# Zio_Qwiic_LoRa_Module.net
KiCad netlist of a schematic drawn in EAGLE
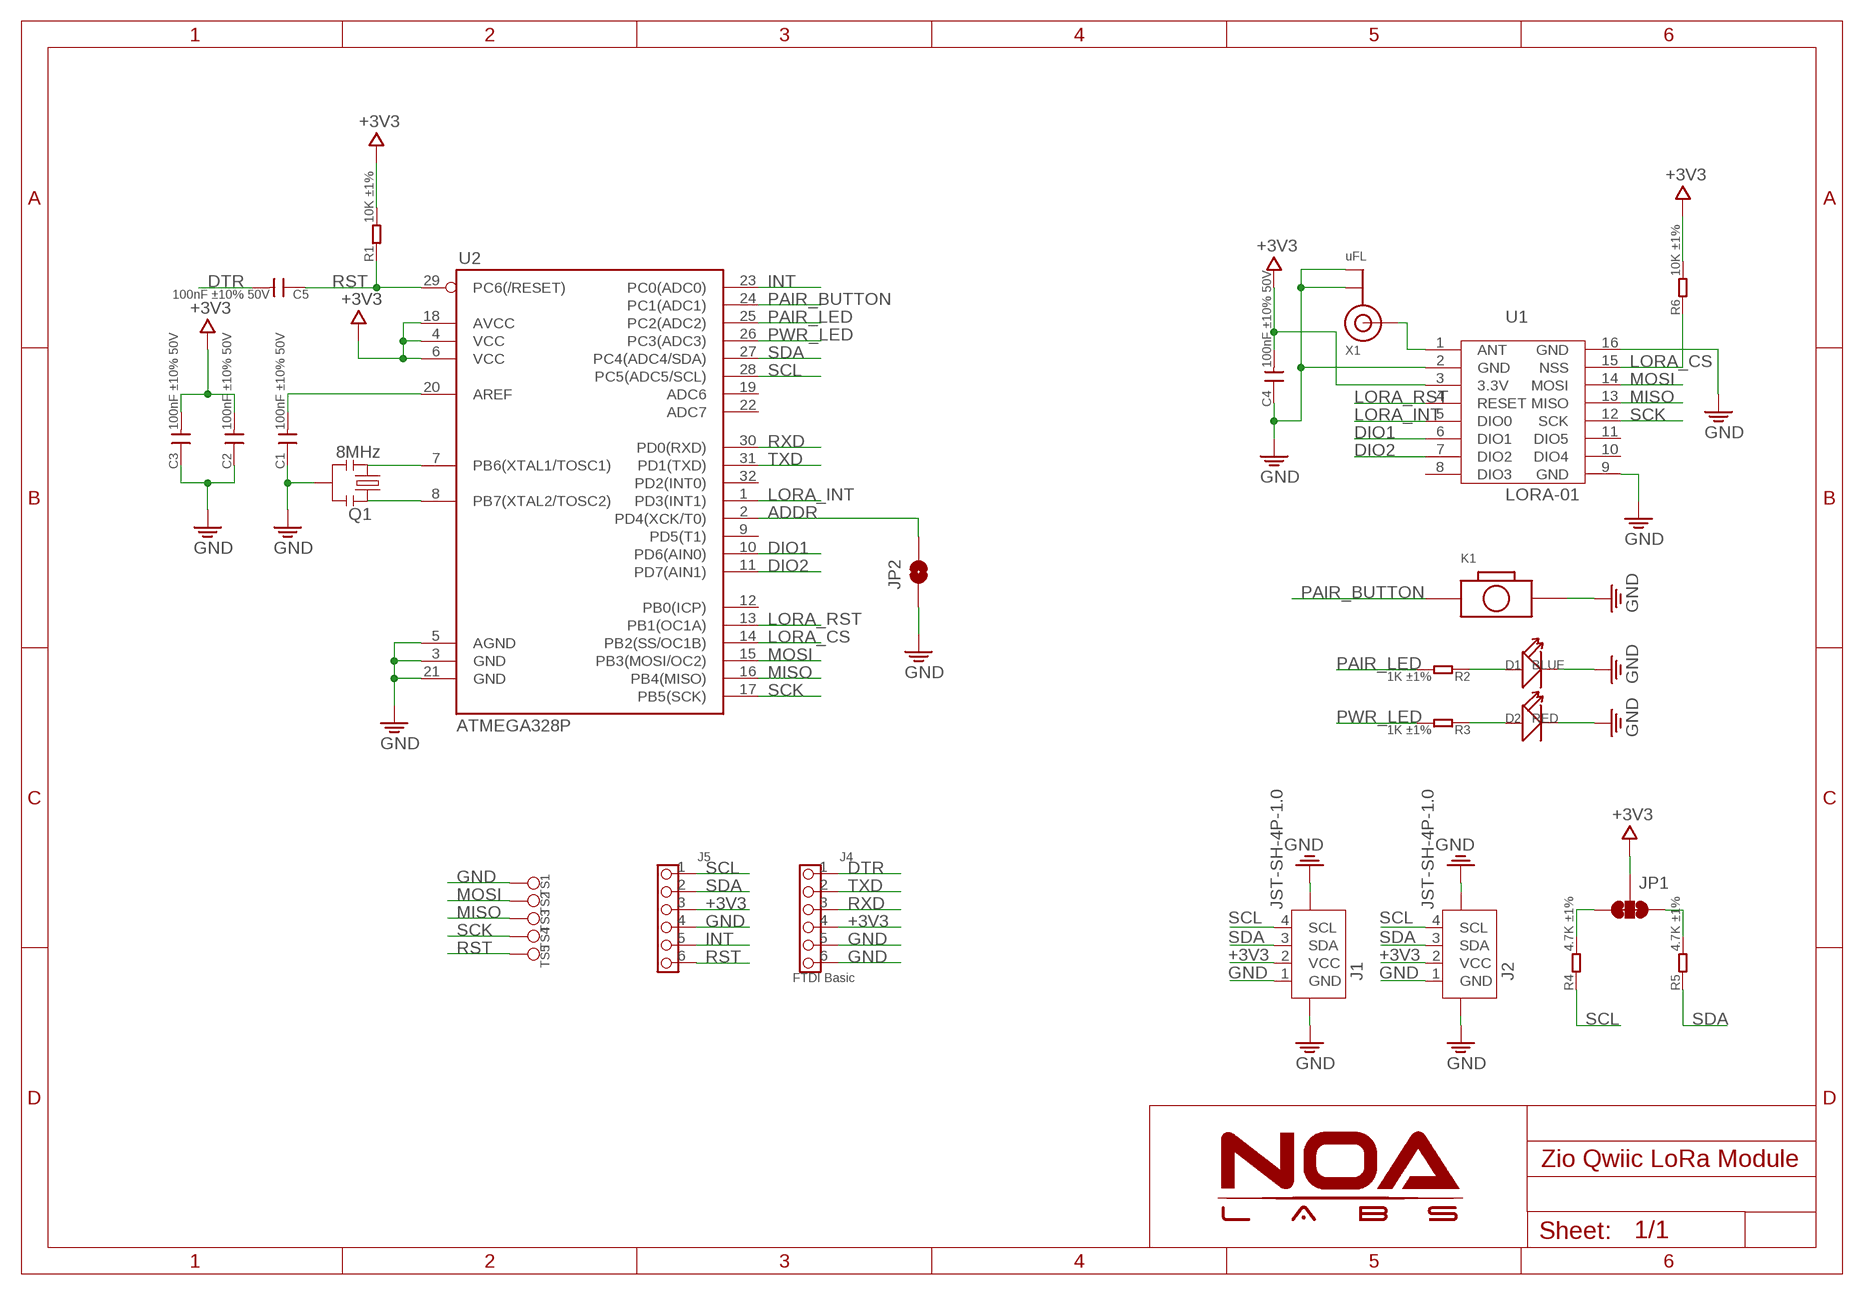
[diagram p0: schematic, sheet 1]

(export (version "E")
  (design (tool "Eeschema 10.0.6"))
  (components
    (comp (ref "C1")
      (value "100nF ±10% 50V")
      (footprint "eagle-import:C0603")
      (libsource (lib "eagle-import") (part "C-0603"))
    )
    (comp (ref "C2")
      (value "100nF ±10% 50V")
      (footprint "eagle-import:C0603")
      (libsource (lib "eagle-import") (part "C-0603"))
    )
    (comp (ref "C3")
      (value "100nF ±10% 50V")
      (footprint "eagle-import:C0603")
      (libsource (lib "eagle-import") (part "C-0603"))
    )
    (comp (ref "C4")
      (value "100nF ±10% 50V")
      (footprint "eagle-import:C0603")
      (libsource (lib "eagle-import") (part "C-0603"))
    )
    (comp (ref "C5")
      (value "100nF ±10% 50V")
      (footprint "eagle-import:C0603")
      (libsource (lib "eagle-import") (part "C-0603"))
    )
    (comp (ref "D1")
      (value "BLUE")
      (footprint "eagle-import:LED-0603")
      (libsource (lib "eagle-import") (part "LED'0603'"))
    )
    (comp (ref "D2")
      (value "RED")
      (footprint "eagle-import:LED-0603")
      (libsource (lib "eagle-import") (part "LED'0603'"))
    )
    (comp (ref "J1")
      (value "JST-SH-4P-1.0")
      (footprint "eagle-import:JST-SH-4P")
      (libsource (lib "eagle-import") (part "JST-SH-4P-1.0"))
    )
    (comp (ref "J2")
      (value "JST-SH-4P-1.0")
      (footprint "eagle-import:JST-SH-4P")
      (libsource (lib "eagle-import") (part "JST-SH-4P-1.0"))
    )
    (comp (ref "J4")
      (value "FTDI Basic")
      (footprint "eagle-import:6P-2.54-60_35MIL")
      (libsource (lib "eagle-import") (part "HEADER-6P-60/35MIL"))
    )
    (comp (ref "J5")
      (value "HEADER-6P-60/35MIL")
      (footprint "eagle-import:6P-2.54-60_35MIL")
      (libsource (lib "eagle-import") (part "HEADER-6P-60/35MIL"))
    )
    (comp (ref "JP1")
      (value "SMT-JUMPER_3_2-NC_TRACE")
      (footprint "eagle-import:SMT-JUMPER_3_2-NC_TRACE")
      (libsource (lib "eagle-import") (part "SMT-JUMPER_3_2-NC_TRACE"))
    )
    (comp (ref "JP2")
      (value "JUMPER-SMT_2_NC_PASTE_NOCREM")
      (footprint "eagle-import:SMT-JUMPER_2_NC_PASTE_SILK_NOCREM")
      (libsource (lib "eagle-import") (part "JUMPER-SMT_2_NC_PASTE_NOCREM"))
    )
    (comp (ref "K1")
      (value "BOTTON-2PSKRKAEE020")
      (footprint "eagle-import:SKRKAEE020")
      (libsource (lib "eagle-import") (part "BOTTON-2PSKRKAEE020"))
    )
    (comp (ref "Q1")
      (value "8MHz")
      (footprint "eagle-import:RESONATOR-SMD")
      (libsource (lib "eagle-import") (part "RESONATORSMD"))
    )
    (comp (ref "R1")
      (value "10K ±1%")
      (footprint "eagle-import:R0603")
      (libsource (lib "eagle-import") (part "R-0603"))
    )
    (comp (ref "R2")
      (value "1K ±1%")
      (footprint "eagle-import:R0603")
      (libsource (lib "eagle-import") (part "R-0603"))
    )
    (comp (ref "R3")
      (value "1K ±1%")
      (footprint "eagle-import:R0603")
      (libsource (lib "eagle-import") (part "R-0603"))
    )
    (comp (ref "R4")
      (value "4.7K ±1%")
      (footprint "eagle-import:R0603")
      (libsource (lib "eagle-import") (part "R-0603"))
    )
    (comp (ref "R5")
      (value "4.7K ±1%")
      (footprint "eagle-import:R0603")
      (libsource (lib "eagle-import") (part "R-0603"))
    )
    (comp (ref "R6")
      (value "10K ±1%")
      (footprint "eagle-import:R0603")
      (libsource (lib "eagle-import") (part "R-0603"))
    )
    (comp (ref "TS1")
      (value "TEST_POINT35MIL")
      (footprint "eagle-import:1P-35MIL")
      (libsource (lib "eagle-import") (part "TEST_POINT35MIL"))
    )
    (comp (ref "TS2")
      (value "TEST_POINT35MIL")
      (footprint "eagle-import:1P-35MIL")
      (libsource (lib "eagle-import") (part "TEST_POINT35MIL"))
    )
    (comp (ref "TS3")
      (value "TEST_POINT35MIL")
      (footprint "eagle-import:1P-35MIL")
      (libsource (lib "eagle-import") (part "TEST_POINT35MIL"))
    )
    (comp (ref "TS4")
      (value "TEST_POINT35MIL")
      (footprint "eagle-import:1P-35MIL")
      (libsource (lib "eagle-import") (part "TEST_POINT35MIL"))
    )
    (comp (ref "TS5")
      (value "TEST_POINT35MIL")
      (footprint "eagle-import:1P-35MIL")
      (libsource (lib "eagle-import") (part "TEST_POINT35MIL"))
    )
    (comp (ref "U1")
      (value "LORA-01")
      (footprint "eagle-import:LORA-01")
      (libsource (lib "eagle-import") (part "LORA-01"))
    )
    (comp (ref "U2")
      (value "ATMEGA328P")
      (footprint "eagle-import:TQFP32-08")
      (libsource (lib "eagle-import") (part "ATMEGA168"))
    )
    (comp (ref "X1")
      (value "uFL")
      (footprint "eagle-import:U.FL")
      (libsource (lib "eagle-import") (part "ANTENNA_U.FL"))
    )
  )
  (nets
    (net (code "1") (name "+3V3") (class "Default")
      (node (ref "C2") (pin "2") (pinfunction "2_2") (pintype "passive"))
      (node (ref "C3") (pin "2") (pinfunction "2_2") (pintype "passive"))
      (node (ref "C4") (pin "2") (pinfunction "2_2") (pintype "passive"))
      (node (ref "J1") (pin "2") (pinfunction "VCC_2") (pintype "bidirectional"))
      (node (ref "J2") (pin "2") (pinfunction "VCC_2") (pintype "bidirectional"))
      (node (ref "J4") (pin "4") (pinfunction "4_4") (pintype "bidirectional"))
      (node (ref "J5") (pin "3") (pinfunction "3_3") (pintype "bidirectional"))
      (node (ref "JP1") (pin "2") (pinfunction "2_2") (pintype "passive"))
      (node (ref "R1") (pin "2") (pinfunction "2_2") (pintype "passive"))
      (node (ref "R6") (pin "2") (pinfunction "2_2") (pintype "passive"))
      (node (ref "U1") (pin "3") (pinfunction "3.3V_3") (pintype "bidirectional"))
      (node (ref "U2") (pin "18") (pinfunction "AVCC_18") (pintype "bidirectional"))
      (node (ref "U2") (pin "4") (pinfunction "VCC_4") (pintype "bidirectional"))
      (node (ref "U2") (pin "6") (pinfunction "VCC_6") (pintype "bidirectional"))
    )
    (net (code "2") (name "/ADDR") (class "Default")
      (node (ref "JP2") (pin "2") (pinfunction "2_2") (pintype "passive"))
      (node (ref "U2") (pin "2") (pinfunction "PD4(XCK/T0)_2") (pintype "bidirectional"))
    )
    (net (code "3") (name "/DIO1") (class "Default")
      (node (ref "U1") (pin "6") (pinfunction "DIO1_6") (pintype "bidirectional"))
      (node (ref "U2") (pin "10") (pinfunction "PD6(AIN0)_10") (pintype "bidirectional"))
    )
    (net (code "4") (name "/DIO2") (class "Default")
      (node (ref "U1") (pin "7") (pinfunction "DIO2_7") (pintype "bidirectional"))
      (node (ref "U2") (pin "11") (pinfunction "PD7(AIN1)_11") (pintype "bidirectional"))
    )
    (net (code "5") (name "/DTR") (class "Default")
      (node (ref "C5") (pin "2") (pinfunction "2_2") (pintype "passive"))
      (node (ref "J4") (pin "1") (pinfunction "1_1") (pintype "bidirectional"))
    )
    (net (code "6") (name "/INT") (class "Default")
      (node (ref "J5") (pin "5") (pinfunction "5_5") (pintype "bidirectional"))
      (node (ref "U2") (pin "23") (pinfunction "PC0(ADC0)_23") (pintype "bidirectional"))
    )
    (net (code "7") (name "/LORA_CS") (class "Default")
      (node (ref "R6") (pin "1") (pinfunction "1_1") (pintype "passive"))
      (node (ref "U1") (pin "15") (pinfunction "NSS_15") (pintype "bidirectional"))
      (node (ref "U2") (pin "14") (pinfunction "PB2(SS/OC1B)_14") (pintype "bidirectional"))
    )
    (net (code "8") (name "/LORA_INT") (class "Default")
      (node (ref "U1") (pin "5") (pinfunction "DIO0_5") (pintype "bidirectional"))
      (node (ref "U2") (pin "1") (pinfunction "PD3(INT1)_1") (pintype "bidirectional"))
    )
    (net (code "9") (name "/LORA_RST") (class "Default")
      (node (ref "U1") (pin "4") (pinfunction "RESET_4") (pintype "bidirectional"))
      (node (ref "U2") (pin "13") (pinfunction "PB1(OC1A)_13") (pintype "bidirectional"))
    )
    (net (code "10") (name "/MISO") (class "Default")
      (node (ref "TS3") (pin "P$1") (pinfunction "1_P$1") (pintype "bidirectional"))
      (node (ref "U1") (pin "13") (pinfunction "MISO_13") (pintype "bidirectional"))
      (node (ref "U2") (pin "16") (pinfunction "PB4(MISO)_16") (pintype "bidirectional"))
    )
    (net (code "11") (name "/MOSI") (class "Default")
      (node (ref "TS2") (pin "P$1") (pinfunction "1_P$1") (pintype "bidirectional"))
      (node (ref "U1") (pin "14") (pinfunction "MOSI_14") (pintype "bidirectional"))
      (node (ref "U2") (pin "15") (pinfunction "PB3(MOSI/OC2)_15") (pintype "bidirectional"))
    )
    (net (code "12") (name "/PAIR_BUTTON") (class "Default")
      (node (ref "K1") (pin "1") (pinfunction "1_1") (pintype "bidirectional"))
      (node (ref "U2") (pin "24") (pinfunction "PC1(ADC1)_24") (pintype "bidirectional"))
    )
    (net (code "13") (name "/PAIR_LED") (class "Default")
      (node (ref "R2") (pin "2") (pinfunction "2_2") (pintype "passive"))
      (node (ref "U2") (pin "25") (pinfunction "PC2(ADC2)_25") (pintype "bidirectional"))
    )
    (net (code "14") (name "/PWR_LED") (class "Default")
      (node (ref "R3") (pin "2") (pinfunction "2_2") (pintype "passive"))
      (node (ref "U2") (pin "26") (pinfunction "PC3(ADC3)_26") (pintype "bidirectional"))
    )
    (net (code "15") (name "/RST") (class "Default")
      (node (ref "C5") (pin "1") (pinfunction "1_1") (pintype "passive"))
      (node (ref "J5") (pin "6") (pinfunction "6_6") (pintype "bidirectional"))
      (node (ref "R1") (pin "1") (pinfunction "1_1") (pintype "passive"))
      (node (ref "TS5") (pin "P$1") (pinfunction "1_P$1") (pintype "bidirectional"))
      (node (ref "U2") (pin "29") (pinfunction "PC6(/RESET)_29") (pintype "bidirectional"))
    )
    (net (code "16") (name "/RXD") (class "Default")
      (node (ref "J4") (pin "3") (pinfunction "3_3") (pintype "bidirectional"))
      (node (ref "U2") (pin "30") (pinfunction "PD0(RXD)_30") (pintype "bidirectional"))
    )
    (net (code "17") (name "/SCK") (class "Default")
      (node (ref "TS4") (pin "P$1") (pinfunction "1_P$1") (pintype "bidirectional"))
      (node (ref "U1") (pin "12") (pinfunction "SCK_12") (pintype "bidirectional"))
      (node (ref "U2") (pin "17") (pinfunction "PB5(SCK)_17") (pintype "bidirectional"))
    )
    (net (code "18") (name "/SCL") (class "Default")
      (node (ref "J1") (pin "4") (pinfunction "SCL_4") (pintype "bidirectional"))
      (node (ref "J2") (pin "4") (pinfunction "SCL_4") (pintype "bidirectional"))
      (node (ref "J5") (pin "1") (pinfunction "1_1") (pintype "bidirectional"))
      (node (ref "R4") (pin "1") (pinfunction "1_1") (pintype "passive"))
      (node (ref "U2") (pin "28") (pinfunction "PC5(ADC5/SCL)_28") (pintype "bidirectional"))
    )
    (net (code "19") (name "/SDA") (class "Default")
      (node (ref "J1") (pin "3") (pinfunction "SDA_3") (pintype "bidirectional"))
      (node (ref "J2") (pin "3") (pinfunction "SDA_3") (pintype "bidirectional"))
      (node (ref "J5") (pin "2") (pinfunction "2_2") (pintype "bidirectional"))
      (node (ref "R5") (pin "1") (pinfunction "1_1") (pintype "passive"))
      (node (ref "U2") (pin "27") (pinfunction "PC4(ADC4/SDA)_27") (pintype "bidirectional"))
    )
    (net (code "20") (name "/TXD") (class "Default")
      (node (ref "J4") (pin "2") (pinfunction "2_2") (pintype "bidirectional"))
      (node (ref "U2") (pin "31") (pinfunction "PD1(TXD)_31") (pintype "bidirectional"))
    )
    (net (code "21") (name "GND") (class "Default")
      (node (ref "C1") (pin "1") (pinfunction "1_1") (pintype "passive"))
      (node (ref "C2") (pin "1") (pinfunction "1_1") (pintype "passive"))
      (node (ref "C3") (pin "1") (pinfunction "1_1") (pintype "passive"))
      (node (ref "C4") (pin "1") (pinfunction "1_1") (pintype "passive"))
      (node (ref "D1") (pin "-") (pinfunction "-_-") (pintype "passive"))
      (node (ref "D2") (pin "-") (pinfunction "-_-") (pintype "passive"))
      (node (ref "J1") (pin "1") (pinfunction "GND_1") (pintype "bidirectional"))
      (node (ref "J1") (pin "NC1") (pinfunction "5_NC1") (pintype "bidirectional"))
      (node (ref "J1") (pin "NC2") (pinfunction "6_NC2") (pintype "bidirectional"))
      (node (ref "J2") (pin "1") (pinfunction "GND_1") (pintype "bidirectional"))
      (node (ref "J2") (pin "NC1") (pinfunction "5_NC1") (pintype "bidirectional"))
      (node (ref "J2") (pin "NC2") (pinfunction "6_NC2") (pintype "bidirectional"))
      (node (ref "J4") (pin "5") (pinfunction "5_5") (pintype "bidirectional"))
      (node (ref "J4") (pin "6") (pinfunction "6_6") (pintype "bidirectional"))
      (node (ref "J5") (pin "4") (pinfunction "4_4") (pintype "bidirectional"))
      (node (ref "JP2") (pin "1") (pinfunction "1_1") (pintype "passive"))
      (node (ref "K1") (pin "2") (pinfunction "2_2") (pintype "bidirectional"))
      (node (ref "Q1") (pin "2") (pinfunction "2_2") (pintype "passive"))
      (node (ref "TS1") (pin "P$1") (pinfunction "1_P$1") (pintype "bidirectional"))
      (node (ref "U1") (pin "16") (pinfunction "GND_16") (pintype "bidirectional"))
      (node (ref "U1") (pin "2") (pinfunction "GND_2") (pintype "bidirectional"))
      (node (ref "U1") (pin "9") (pinfunction "GND_9") (pintype "bidirectional"))
      (node (ref "U2") (pin "21") (pinfunction "GND_21") (pintype "bidirectional"))
      (node (ref "U2") (pin "3") (pinfunction "GND_3") (pintype "bidirectional"))
      (node (ref "U2") (pin "5") (pinfunction "AGND_5") (pintype "bidirectional"))
      (node (ref "X1") (pin "1") (pinfunction "GND_1") (pintype "passive"))
      (node (ref "X1") (pin "2") (pinfunction "GND_2") (pintype "passive"))
    )
    (net (code "22") (name "Net-(D1-Pad+)") (class "Default")
      (node (ref "D1") (pin "+") (pinfunction "+_+") (pintype "passive"))
      (node (ref "R2") (pin "1") (pinfunction "1_1") (pintype "passive"))
    )
    (net (code "23") (name "Net-(D2-Pad+)") (class "Default")
      (node (ref "D2") (pin "+") (pinfunction "+_+") (pintype "passive"))
      (node (ref "R3") (pin "1") (pinfunction "1_1") (pintype "passive"))
    )
    (net (code "24") (name "Net-(JP1-Pad1)") (class "Default")
      (node (ref "JP1") (pin "1") (pinfunction "1_1") (pintype "passive"))
      (node (ref "R5") (pin "2") (pinfunction "2_2") (pintype "passive"))
    )
    (net (code "25") (name "Net-(JP1-Pad3)") (class "Default")
      (node (ref "JP1") (pin "3") (pinfunction "3_3") (pintype "passive"))
      (node (ref "R4") (pin "2") (pinfunction "2_2") (pintype "passive"))
    )
    (net (code "26") (name "Net-(U1-ANT)") (class "Default")
      (node (ref "U1") (pin "1") (pinfunction "ANT_1") (pintype "bidirectional"))
      (node (ref "X1") (pin "3") (pinfunction "SIGNAL_3") (pintype "passive"))
    )
    (net (code "27") (name "Net-(U2-AREF)") (class "Default")
      (node (ref "C1") (pin "2") (pinfunction "2_2") (pintype "passive"))
      (node (ref "U2") (pin "20") (pinfunction "AREF_20") (pintype "bidirectional"))
    )
    (net (code "28") (name "Net-(U2-PB6(XTAL1{slash}TOSC1))") (class "Default")
      (node (ref "Q1") (pin "3") (pinfunction "3_3") (pintype "passive"))
      (node (ref "U2") (pin "7") (pinfunction "PB6(XTAL1/TOSC1)_7") (pintype "bidirectional"))
    )
    (net (code "29") (name "Net-(U2-PB7(XTAL2{slash}TOSC2))") (class "Default")
      (node (ref "Q1") (pin "1") (pinfunction "1_1") (pintype "passive"))
      (node (ref "U2") (pin "8") (pinfunction "PB7(XTAL2/TOSC2)_8") (pintype "bidirectional"))
    )
    (net (code "30") (name "unconnected-(U1-DIO3-Pad8)") (class "Default")
      (node (ref "U1") (pin "8") (pinfunction "DIO3_8") (pintype "bidirectional"))
    )
    (net (code "31") (name "unconnected-(U1-DIO4-Pad10)") (class "Default")
      (node (ref "U1") (pin "10") (pinfunction "DIO4_10") (pintype "bidirectional"))
    )
    (net (code "32") (name "unconnected-(U1-DIO5-Pad11)") (class "Default")
      (node (ref "U1") (pin "11") (pinfunction "DIO5_11") (pintype "bidirectional"))
    )
    (net (code "33") (name "unconnected-(U2-ADC6-Pad19)") (class "Default")
      (node (ref "U2") (pin "19") (pinfunction "ADC6_19") (pintype "bidirectional"))
    )
    (net (code "34") (name "unconnected-(U2-ADC7-Pad22)") (class "Default")
      (node (ref "U2") (pin "22") (pinfunction "ADC7_22") (pintype "bidirectional"))
    )
    (net (code "35") (name "unconnected-(U2-PB0(ICP)-Pad12)") (class "Default")
      (node (ref "U2") (pin "12") (pinfunction "PB0(ICP)_12") (pintype "bidirectional"))
    )
    (net (code "36") (name "unconnected-(U2-PD2(INT0)-Pad32)") (class "Default")
      (node (ref "U2") (pin "32") (pinfunction "PD2(INT0)_32") (pintype "bidirectional"))
    )
    (net (code "37") (name "unconnected-(U2-PD5(T1)-Pad9)") (class "Default")
      (node (ref "U2") (pin "9") (pinfunction "PD5(T1)_9") (pintype "bidirectional"))
    )
  )
)
